# ChaiNEO_FrontConn_Gem.net
KiCad netlist of a schematic drawn in EAGLE
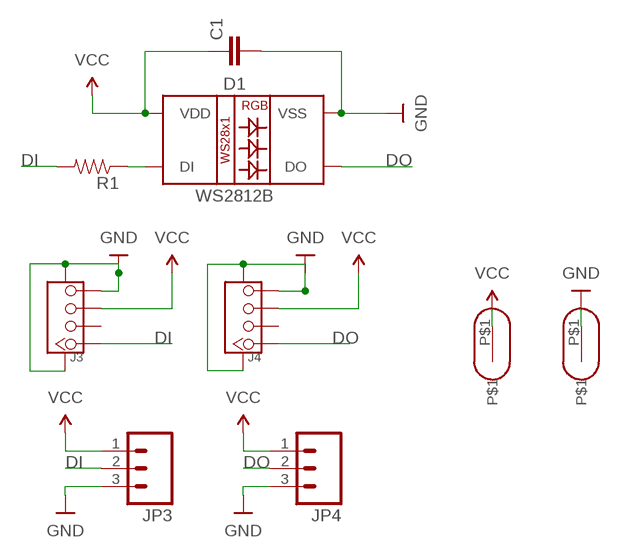
[diagram p0: schematic, sheet 1]

(export (version "E")
  (design (tool "Eeschema 10.0.6"))
  (components
    (comp (ref "C1")
      (value "CAP0603-CAP")
      (footprint "eagle-import:0603-CAP")
      (libsource (lib "eagle-import") (part "CAP0603-CAP"))
    )
    (comp (ref "D1")
      (value "WS2812B")
      (footprint "eagle-import:WS2812B")
      (libsource (lib "eagle-import") (part "WS2812B"))
    )
    (comp (ref "J3")
      (value "TWIG-4P-2.0-SMD-FEMALE-REINFORCE90D")
      (footprint "eagle-import:4P-SMD-2.0-90D")
      (libsource (lib "eagle-import") (part "TWIG-4P-2.0-SMD-FEMALE-REINFORCE90D"))
    )
    (comp (ref "J4")
      (value "TWIG-4P-2.0-SMD-FEMALE-REINFORCE90D")
      (footprint "eagle-import:4P-SMD-2.0-90D")
      (libsource (lib "eagle-import") (part "TWIG-4P-2.0-SMD-FEMALE-REINFORCE90D"))
    )
    (comp (ref "JP3")
      (value "M03LONGPADS")
      (footprint "eagle-import:1X03_LONGPADS")
      (libsource (lib "eagle-import") (part "M03LONGPADS"))
    )
    (comp (ref "JP4")
      (value "M03LONGPADS")
      (footprint "eagle-import:1X03_LONGPADS")
      (libsource (lib "eagle-import") (part "M03LONGPADS"))
    )
    (comp (ref "R1")
      (value "RESISTOR0603-RES")
      (footprint "eagle-import:0603-RES")
      (libsource (lib "eagle-import") (part "RESISTOR0603-RES"))
    )
    (comp (ref "U$7")
      (value "PLATED_TIE_MOUNT")
      (footprint "eagle-import:PLATED_TIE_MOUNT")
      (libsource (lib "eagle-import") (part "PLATED_TIE_MOUNT"))
    )
    (comp (ref "U$8")
      (value "PLATED_TIE_MOUNT")
      (footprint "eagle-import:PLATED_TIE_MOUNT")
      (libsource (lib "eagle-import") (part "PLATED_TIE_MOUNT"))
    )
  )
  (nets
    (net (code "1") (name "/DI") (class "Default")
      (node (ref "J3") (pin "1") (pinfunction "1_1") (pintype "bidirectional"))
      (node (ref "JP3") (pin "2") (pinfunction "2_2") (pintype "passive"))
      (node (ref "R1") (pin "2") (pinfunction "2_2") (pintype "passive"))
    )
    (net (code "2") (name "/DO") (class "Default")
      (node (ref "D1") (pin "2") (pinfunction "DO_2") (pintype "bidirectional"))
      (node (ref "J4") (pin "1") (pinfunction "1_1") (pintype "bidirectional"))
      (node (ref "JP4") (pin "2") (pinfunction "2_2") (pintype "passive"))
    )
    (net (code "3") (name "GND") (class "Default")
      (node (ref "C1") (pin "2") (pinfunction "2_2") (pintype "passive"))
      (node (ref "D1") (pin "3") (pinfunction "VSS_3") (pintype "bidirectional"))
      (node (ref "J3") (pin "4") (pinfunction "4_4") (pintype "bidirectional"))
      (node (ref "J3") (pin "SS1") (pinfunction "SS1_SS1") (pintype "bidirectional"))
      (node (ref "J3") (pin "SS2") (pinfunction "SS2_SS2") (pintype "bidirectional"))
      (node (ref "J4") (pin "4") (pinfunction "4_4") (pintype "bidirectional"))
      (node (ref "J4") (pin "SS1") (pinfunction "SS1_SS1") (pintype "bidirectional"))
      (node (ref "J4") (pin "SS2") (pinfunction "SS2_SS2") (pintype "bidirectional"))
      (node (ref "JP3") (pin "3") (pinfunction "3_3") (pintype "passive"))
      (node (ref "JP4") (pin "3") (pinfunction "3_3") (pintype "passive"))
      (node (ref "U$8") (pin "P$1") (pinfunction "P$1_P$1") (pintype "bidirectional"))
    )
    (net (code "4") (name "Net-(D1-DI)") (class "Default")
      (node (ref "D1") (pin "4") (pinfunction "DI_4") (pintype "bidirectional"))
      (node (ref "R1") (pin "1") (pinfunction "1_1") (pintype "passive"))
    )
    (net (code "5") (name "VCC") (class "Default")
      (node (ref "C1") (pin "1") (pinfunction "1_1") (pintype "passive"))
      (node (ref "D1") (pin "1") (pinfunction "VDD_1") (pintype "bidirectional"))
      (node (ref "J3") (pin "3") (pinfunction "3_3") (pintype "bidirectional"))
      (node (ref "J4") (pin "3") (pinfunction "3_3") (pintype "bidirectional"))
      (node (ref "JP3") (pin "1") (pinfunction "1_1") (pintype "passive"))
      (node (ref "JP4") (pin "1") (pinfunction "1_1") (pintype "passive"))
      (node (ref "U$7") (pin "P$1") (pinfunction "P$1_P$1") (pintype "bidirectional"))
    )
    (net (code "6") (name "unconnected-(J3-Pad2)") (class "Default")
      (node (ref "J3") (pin "2") (pinfunction "2_2") (pintype "bidirectional"))
    )
    (net (code "7") (name "unconnected-(J4-Pad2)") (class "Default")
      (node (ref "J4") (pin "2") (pinfunction "2_2") (pintype "bidirectional"))
    )
  )
)
